# CAN_Adaptor.net
KiCad netlist of a schematic drawn in Altium Designer
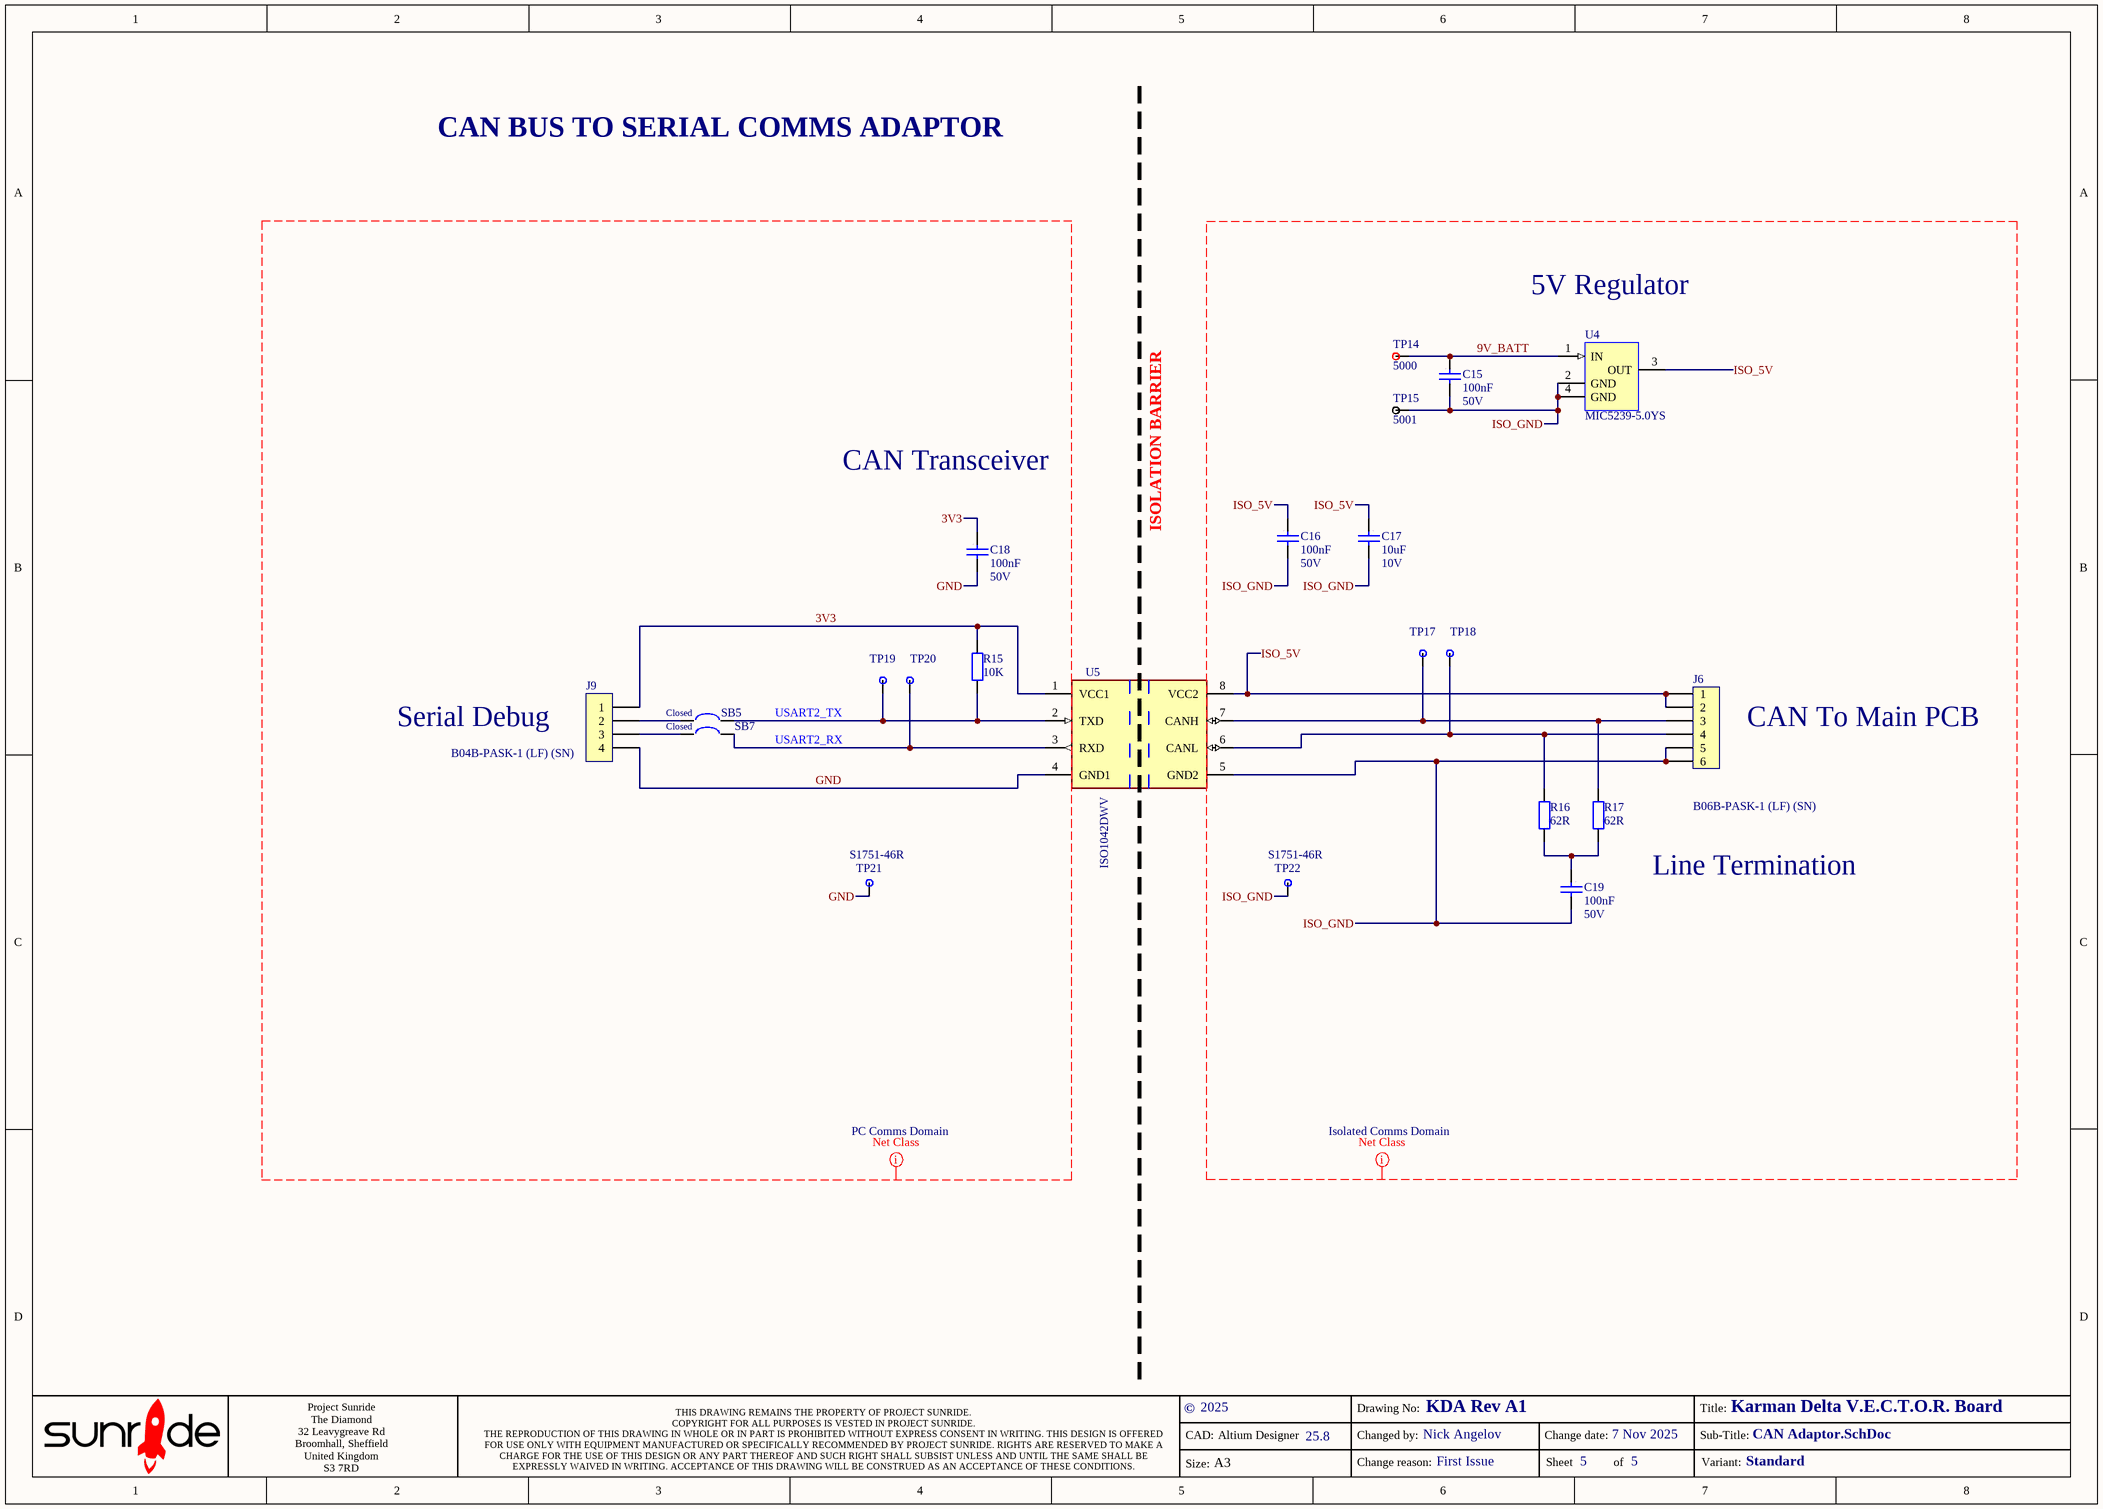
[diagram p0: CAN Adaptor.SchDoc]

(export (version "E")
  (design (tool "Eeschema 10.0.6"))
  (components
    (comp (ref "C15")
      (value "100nF")
      (footprint "CAPC1608X08L")
      (description "Capacitor MLC 100nF 50V X7R 10% CAPC1608X08M")
      (fields
        (field (name "VOLTAGE") "50V")
        (field (name "MANUFACTURER") "Murata")
        (field (name "MANUPARTNO") "GRM188R71H104KA93D")
      )
      (libsource (lib "Library") (part "CAP"))
    )
    (comp (ref "C16")
      (value "100nF")
      (footprint "CAPC1608X08L")
      (description "Capacitor MLC 100nF 50V X7R 10% CAPC1608X08M")
      (fields
        (field (name "VOLTAGE") "50V")
        (field (name "MANUFACTURER") "Murata")
        (field (name "MANUPARTNO") "GRM188R71H104KA93D")
      )
      (libsource (lib "Library") (part "CAP"))
    )
    (comp (ref "C17")
      (value "10uF")
      (footprint "CAPC2012X15M")
      (description "Capacitor MLC 10uF10V X7R 10% CAPC2012X15M")
      (fields
        (field (name "VOLTAGE") "10V")
        (field (name "MANUFACTURER") "Murata")
        (field (name "MANUPARTNO") "GRM21BR71A106KE51L")
      )
      (libsource (lib "") (part "CAP_1"))
    )
    (comp (ref "C18")
      (value "100nF")
      (footprint "CAPC1608X08L")
      (description "Capacitor MLC 100nF 50V X7R 10% CAPC1608X08M")
      (fields
        (field (name "VOLTAGE") "50V")
        (field (name "MANUFACTURER") "Murata")
        (field (name "MANUPARTNO") "GRM188R71H104KA93D")
      )
      (libsource (lib "Library") (part "CAP"))
    )
    (comp (ref "C19")
      (value "100nF")
      (footprint "CAPC1608X08L")
      (description "Capacitor MLC 100nF 50V X7R 10% CAPC1608X08M")
      (fields
        (field (name "VOLTAGE") "50V")
        (field (name "MANUFACTURER") "Murata")
        (field (name "MANUPARTNO") "GRM188R71H104KA93D")
      )
      (libsource (lib "") (part "CAP_1"))
    )
    (comp (ref "J6")
      (value "CAN To Main PCB")
      (footprint "B06B-PASK-1")
      (description "Connector 6 Way Vertical B06B-PASK-1 (LF) (SN) 2mm Pitch")
      (fields (field (name "MANUPARTNO") "B06B-PASK-1 (LF) (SN)") (field (name "MANUFACTURER") "JST"))
      (libsource (lib "Library") (part "CON6"))
    )
    (comp (ref "J9")
      (value "Serial Debug")
      (footprint "B04B-PASK-1")
      (description "Connector 4 Way Vertical JST B04B-PASK-1 (LF) (SN) 2mm Pitch")
      (fields (field (name "MANUPARTNO") "B04B-PASK-1 (LF) (SN)") (field (name "MANUFACTURER") "JST"))
      (libsource (lib "Library") (part "CON4"))
    )
    (comp (ref "R15")
      (value "10K")
      (footprint "RESC1608X06L")
      (description "SMD Chip Resistor, Thin Film, 10 kohm, 75 V, 0603 [1608 Metric], 100 mW, ± 0.1%, ERA3A Series")
      (fields (field (name "VOLTAGE") "75V") (field (name "MANUFACTURER") "Panasonic"))
      (libsource (lib "Library") (part "RESISTOR"))
    )
    (comp (ref "R16")
      (value "62R")
      (footprint "RESC1608X06L")
      (description "SMD Chip Resistor, Thick Film, 62 ohm, 75V, 0603 [1608 Metric], 100mW, ± 1%, RC Series")
      (fields (field (name "VOLTAGE") "75V") (field (name "POWER") "100mW"))
      (libsource (lib "Library") (part "RESISTOR"))
    )
    (comp (ref "R17")
      (value "Line Termination")
      (footprint "RESC1608X06L")
      (description "SMD Chip Resistor, Thick Film, 62 ohm, 75V, 0603 [1608 Metric], 100mW, ± 1%, RC Series")
      (fields
        (field (name "ALTIUM_VALUE") "62R")
        (field (name "VOLTAGE") "75V")
        (field (name "POWER") "100mW")
      )
      (libsource (lib "Library") (part "RESISTOR"))
    )
    (comp (ref "SB5")
      (value "Solder Blob Closed")
      (footprint "0603SolderLinkClosed")
      (description "Solder Blob - Closed 0603 SM pads")
      (libsource (lib "Library") (part "Solder Blob Closed"))
    )
    (comp (ref "SB7")
      (value "Solder Blob Closed")
      (footprint "0603SolderLinkClosed")
      (description "Solder Blob - Closed 0603 SM pads")
      (libsource (lib "Library") (part "Solder Blob Closed"))
    )
    (comp (ref "TP14")
      (value "+9V")
      (footprint "POST-Red")
      (description "Connector Test Point Red Keystone 5000")
      (fields (field (name "MANUPARTNO") "5000") (field (name "MANUFACTURER") "Keystone"))
      (libsource (lib "Library") (part "TP5000"))
    )
    (comp (ref "TP15")
      (value "0V")
      (footprint "POST-Black")
      (description "Connector Test Point Black Keystone 5001")
      (fields (field (name "MANUPARTNO") "5001") (field (name "MANUFACTURER") "Keystone"))
      (libsource (lib "Library") (part "TP5001"))
    )
    (comp (ref "TP17")
      (value "TMS")
      (footprint "TP1")
      (description "Testpoint 1mm dia. Component side, no silk")
      (libsource (lib "Library") (part "TP1"))
    )
    (comp (ref "TP18")
      (value "TMS")
      (footprint "TP1")
      (description "Testpoint 1mm dia. Component side, no silk")
      (libsource (lib "Library") (part "TP1"))
    )
    (comp (ref "TP19")
      (value "TMS")
      (footprint "TP1")
      (description "Testpoint 1mm dia. Component side, no silk")
      (libsource (lib "Library") (part "TP1"))
    )
    (comp (ref "TP20")
      (value "TMS")
      (footprint "TP1")
      (description "Testpoint 1mm dia. Component side, no silk")
      (libsource (lib "Library") (part "TP1"))
    )
    (comp (ref "TP21")
      (value "GND")
      (footprint "S1751-46R")
      (description "PCB Test Point S1751 Series, Surface Mount")
      (fields (field (name "MANUPARTNO") "S1751-46R") (field (name "MANUFACTURER") "Harwin"))
      (libsource (lib "Library") (part "TP1-fitted"))
    )
    (comp (ref "TP22")
      (value "GND")
      (footprint "S1751-46R")
      (description "PCB Test Point S1751 Series, Surface Mount")
      (fields (field (name "MANUPARTNO") "S1751-46R") (field (name "MANUFACTURER") "Harwin"))
      (libsource (lib "Library") (part "TP1-fitted"))
    )
    (comp (ref "U4")
      (value "5V Regulator")
      (footprint "SOT230P700X170-4M")
      (description "IC Regulator LDO MIC5239-5.0YS SOT-223")
      (fields (field (name "MANUPARTNO") "MIC5239-5.0YS") (field (name "MANUFACTURER") "Micrel"))
      (libsource (lib "Library") (part "MIC5200"))
    )
    (comp (ref "U5")
      (value "CAN Transceiver")
      (footprint "FP-DWV0008A-IPC_C")
      (description "IC TRANSCEIVER FULL 1/1 8SOIC")
      (fields (field (name "MANUF PART NO") "ISO1042DWV"))
      (libsource (lib "Altium Content Vault") (part "909e5d76d32ef4d3bd4dfdc3f0018f8"))
    )
  )
  (nets
    (net (code "1") (name "/3V3") (class "Default")
      (node (ref "C18") (pin "1") (pinfunction "1_1") (pintype "passive"))
      (node (ref "J9") (pin "1") (pinfunction "1_1") (pintype "passive"))
      (node (ref "R15") (pin "2") (pinfunction "2_2") (pintype "passive"))
      (node (ref "U5") (pin "1") (pinfunction "VCC1_1") (pintype "power_in"))
    )
    (net (code "2") (name "/9V_BATT") (class "Default")
      (node (ref "C15") (pin "1") (pinfunction "1_1") (pintype "passive"))
      (node (ref "TP14") (pin "1") (pintype "passive"))
      (node (ref "U4") (pin "1") (pinfunction "IN_1") (pintype "input"))
    )
    (net (code "3") (name "/GND") (class "Default")
      (node (ref "C18") (pin "2") (pinfunction "2_2") (pintype "passive"))
      (node (ref "J9") (pin "4") (pinfunction "4_4") (pintype "passive"))
      (node (ref "TP21") (pin "1") (pintype "passive"))
      (node (ref "U5") (pin "4") (pinfunction "GND1_4") (pintype "power_in"))
    )
    (net (code "4") (name "/ISO_5V") (class "Default")
      (node (ref "C16") (pin "1") (pinfunction "1_1") (pintype "passive"))
      (node (ref "C17") (pin "1") (pinfunction "1_1") (pintype "passive"))
      (node (ref "J6") (pin "1") (pinfunction "1_1") (pintype "passive"))
      (node (ref "J6") (pin "2") (pinfunction "2_2") (pintype "passive"))
      (node (ref "U4") (pin "3") (pinfunction "OUT_3") (pintype "power_in"))
      (node (ref "U5") (pin "8") (pinfunction "VCC2_8") (pintype "power_in"))
    )
    (net (code "5") (name "/ISO_GND") (class "Default")
      (node (ref "C15") (pin "2") (pinfunction "2_2") (pintype "passive"))
      (node (ref "C16") (pin "2") (pinfunction "2_2") (pintype "passive"))
      (node (ref "C17") (pin "2") (pinfunction "2_2") (pintype "passive"))
      (node (ref "C19") (pin "2") (pinfunction "2_2") (pintype "passive"))
      (node (ref "J6") (pin "5") (pinfunction "5_5") (pintype "passive"))
      (node (ref "J6") (pin "6") (pinfunction "6_6") (pintype "passive"))
      (node (ref "TP15") (pin "1") (pintype "passive"))
      (node (ref "TP22") (pin "1") (pintype "passive"))
      (node (ref "U4") (pin "2") (pinfunction "GND_2") (pintype "passive"))
      (node (ref "U4") (pin "4") (pinfunction "GND_4") (pintype "passive"))
      (node (ref "U5") (pin "5") (pinfunction "GND2_5") (pintype "power_in"))
    )
    (net (code "6") (name "Net-(C19-Pad1)") (class "Default")
      (node (ref "C19") (pin "1") (pinfunction "1_1") (pintype "passive"))
      (node (ref "R16") (pin "1") (pinfunction "1_1") (pintype "passive"))
      (node (ref "R17") (pin "1") (pinfunction "1_1") (pintype "passive"))
    )
    (net (code "7") (name "Net-(J9-Pad2)") (class "Default")
      (node (ref "J9") (pin "2") (pinfunction "2_2") (pintype "passive"))
      (node (ref "SB5") (pin "1") (pinfunction "1_1") (pintype "passive"))
    )
    (net (code "8") (name "Net-(J9-Pad3)") (class "Default")
      (node (ref "J9") (pin "3") (pinfunction "3_3") (pintype "passive"))
      (node (ref "SB7") (pin "1") (pinfunction "1_1") (pintype "passive"))
    )
    (net (code "9") (name "Net-(U5-CANH)") (class "Default")
      (node (ref "J6") (pin "3") (pinfunction "3_3") (pintype "passive"))
      (node (ref "R17") (pin "2") (pinfunction "2_2") (pintype "passive"))
      (node (ref "TP17") (pin "1") (pintype "passive"))
      (node (ref "U5") (pin "7") (pinfunction "CANH_7") (pintype "bidirectional"))
    )
    (net (code "10") (name "Net-(U5-CANL)") (class "Default")
      (node (ref "J6") (pin "4") (pinfunction "4_4") (pintype "passive"))
      (node (ref "R16") (pin "2") (pinfunction "2_2") (pintype "passive"))
      (node (ref "TP18") (pin "1") (pintype "passive"))
      (node (ref "U5") (pin "6") (pinfunction "CANL_6") (pintype "bidirectional"))
    )
    (net (code "11") (name "Net-(U5-RXD)") (class "Default")
      (node (ref "SB7") (pin "2") (pinfunction "2_2") (pintype "passive"))
      (node (ref "TP20") (pin "1") (pintype "passive"))
      (node (ref "U5") (pin "3") (pinfunction "RXD_3") (pintype "output"))
    )
    (net (code "12") (name "Net-(U5-TXD)") (class "Default")
      (node (ref "R15") (pin "1") (pinfunction "1_1") (pintype "passive"))
      (node (ref "SB5") (pin "2") (pinfunction "2_2") (pintype "passive"))
      (node (ref "TP19") (pin "1") (pintype "passive"))
      (node (ref "U5") (pin "2") (pinfunction "TXD_2") (pintype "input"))
    )
  )
)
